# Filter.net
KiCad netlist of a schematic drawn in Altium Designer
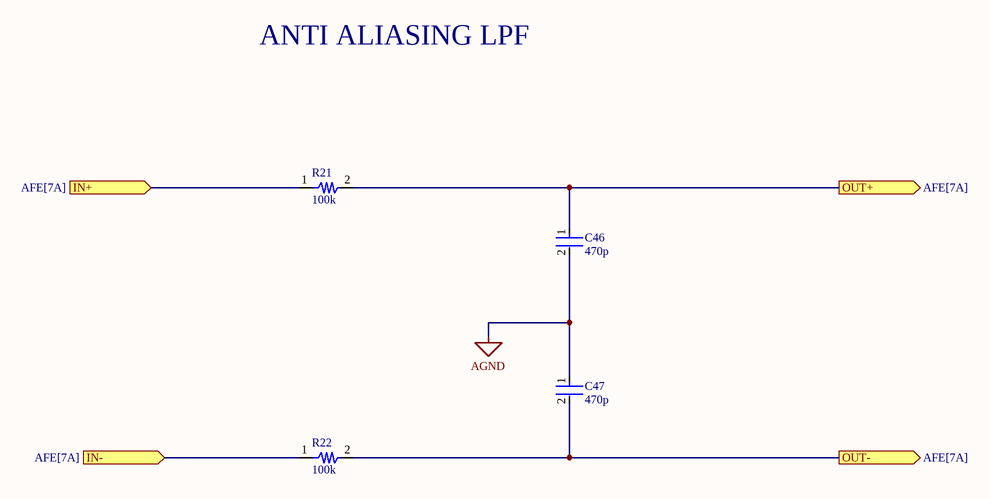
[diagram p0: Filter.SchDoc]

(export (version "E")
  (design (tool "Eeschema 10.0.6"))
  (components
    (comp (ref "C46")
      (value "470p")
      (footprint "FP-C0603C-CF-MFG")
      (description "C0603 470 pF C0G 30ppm/°C 1.00% 100 V")
      (fields
        (field (name "MANUFACTURER") "KEMET")
        (field (name "OCTOPART") "https://octopart.com/c0603c471f1gactu-kemet-26647159")
      )
      (libsource (lib "Altium Content Vault") (part "b4654b650e69147ec39a6b967a45e02"))
    )
    (comp (ref "C47")
      (value "470p")
      (footprint "FP-C0603C-CF-MFG")
      (description "C0603 470 pF C0G 30ppm/°C 1.00% 100 V")
      (fields
        (field (name "MANUFACTURER") "KEMET")
        (field (name "OCTOPART") "https://octopart.com/c0603c471f1gactu-kemet-26647159")
      )
      (libsource (lib "Altium Content Vault") (part "b4654b650e69147ec39a6b967a45e02"))
    )
    (comp (ref "R21")
      (value "100k")
      (footprint "R-1608 [0603]-M")
      (description "Expensive: P2TC0603D1003LNTA - 0.01% Cheap: TNPU0603100KAYEN00 - 0.05%")
      (libsource (lib "EMG_Sensor") (part "Precision_Resistor"))
    )
    (comp (ref "R22")
      (value "100k")
      (footprint "R-1608 [0603]-M")
      (description "Expensive: P2TC0603D1003LNTA - 0.01% Cheap: TNPU0603100KAYEN00 - 0.05%")
      (libsource (lib "EMG_Sensor") (part "Precision_Resistor"))
    )
  )
  (nets
    (net (code "1") (name "/IN+") (class "Default")
      (node (ref "R21") (pin "1") (pinfunction "9_1") (pintype "passive"))
    )
    (net (code "2") (name "/IN-") (class "Default")
      (node (ref "R22") (pin "1") (pinfunction "9_1") (pintype "passive"))
    )
    (net (code "3") (name "/OUT+") (class "Default")
      (node (ref "C46") (pin "1") (pinfunction "1_1") (pintype "passive"))
      (node (ref "R21") (pin "2") (pinfunction "10_2") (pintype "passive"))
    )
    (net (code "4") (name "/OUT-") (class "Default")
      (node (ref "C47") (pin "2") (pinfunction "2_2") (pintype "passive"))
      (node (ref "R22") (pin "2") (pinfunction "10_2") (pintype "passive"))
    )
    (net (code "5") (name "AGND") (class "Default")
      (node (ref "C46") (pin "2") (pinfunction "2_2") (pintype "passive"))
      (node (ref "C47") (pin "1") (pinfunction "1_1") (pintype "passive"))
    )
  )
)
